# power_supply.net
KiCad netlist of a schematic drawn in Altium Designer
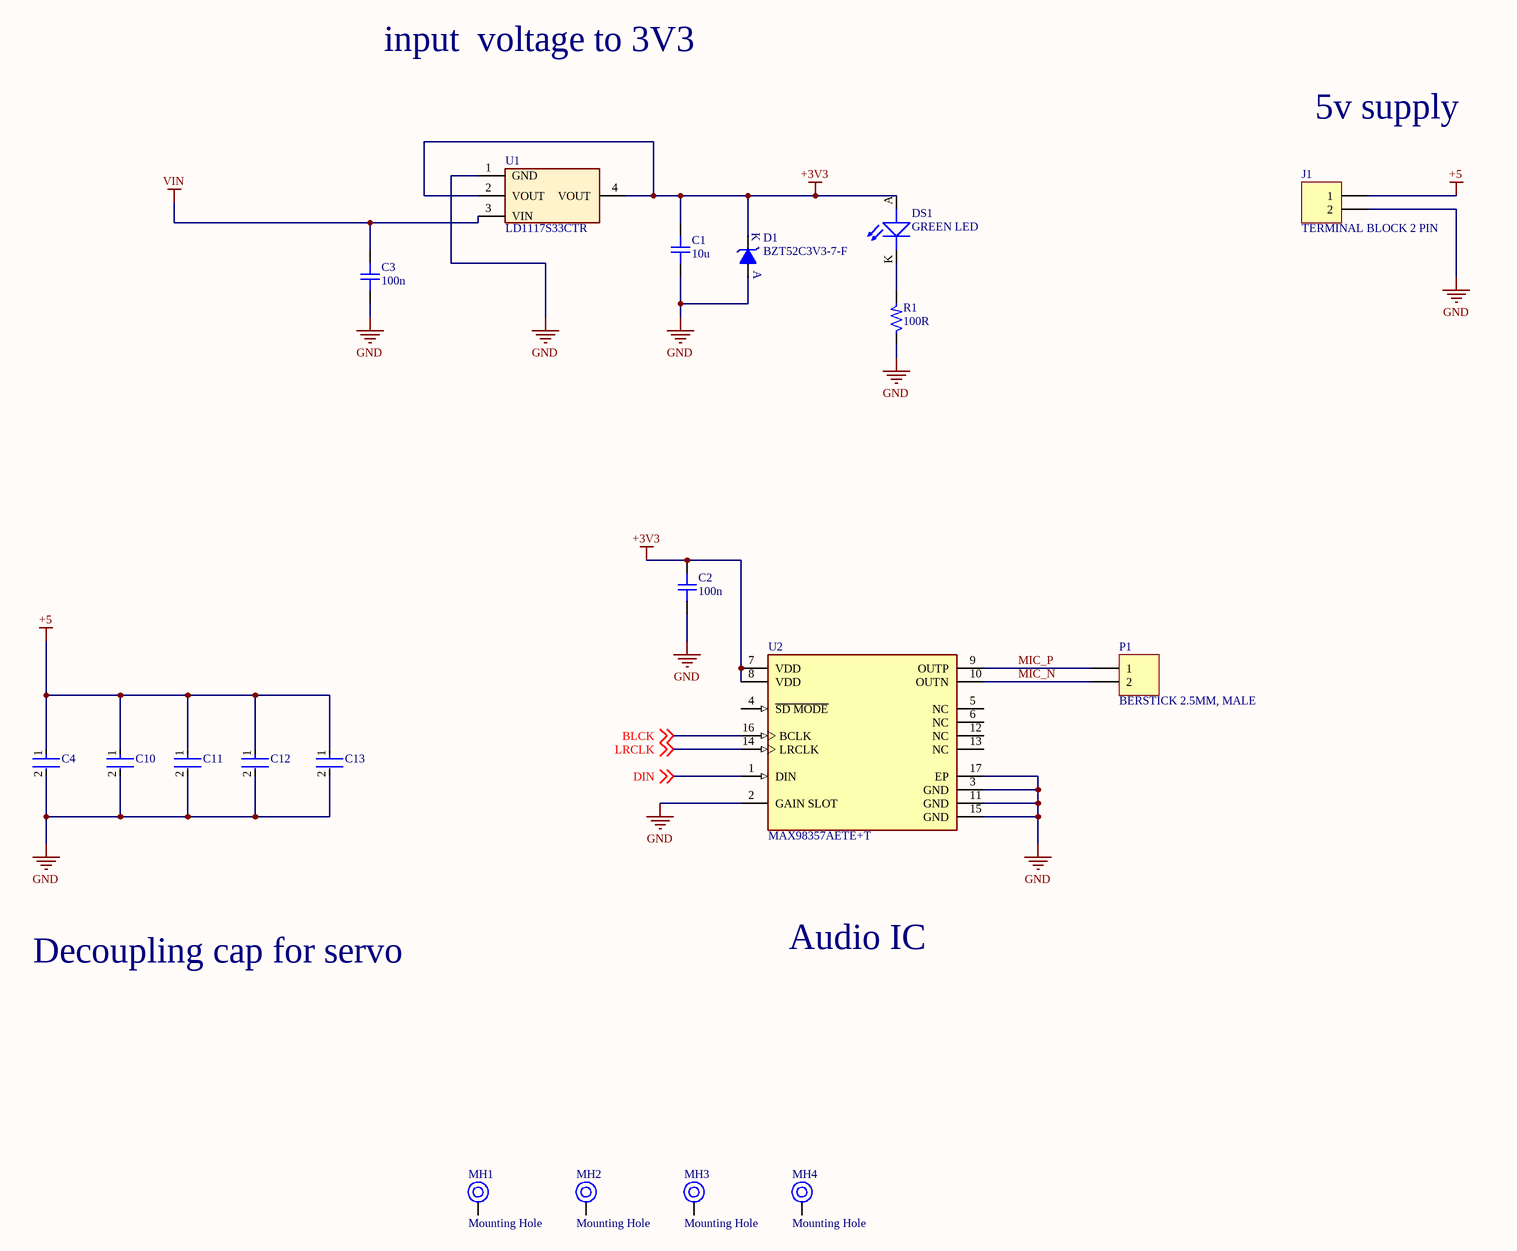
[diagram p0: power supply.SchDoc]

(export (version "E")
  (design (tool "Eeschema 10.0.6"))
  (components
    (comp (ref "C1")
      (value "10u")
      (footprint "CAP_0603")
      (description "Capacitor SMD 0603 10V")
      (fields
        (field (name "MANUFACTURER") "Samsung")
        (field (name "MANUFACTURER PART NUMBER") "CL10A106KP8NNNC")
      )
      (libsource (lib "ESP32_USB_Dongle") (part "CAP_0603_10V"))
    )
    (comp (ref "C2")
      (value "100n")
      (footprint "CAP_0402")
      (description "Capacitor SMD 0402 50V")
      (fields
        (field (name "MANUFACTURER") "Samsung")
        (field (name "MANUFACTURER PART NUMBER") "CL05B104KO5NNNC")
      )
      (libsource (lib "ESP32_USB_Dongle") (part "CAP_0402_50V_1"))
    )
    (comp (ref "C3")
      (value "100n")
      (footprint "CAP_0402")
      (description "Capacitor SMD 0402 50V")
      (fields
        (field (name "MANUFACTURER") "Samsung")
        (field (name "MANUFACTURER PART NUMBER") "CL05B104KO5NNNC")
      )
      (libsource (lib "ESP32_USB_Dongle") (part "CAP_0402_50V_1"))
    )
    (comp (ref "C4")
      (value "C1210C107M9PACTU")
      (footprint "FP-C1210C107M9PACTU-MFG")
      (description "CAP CER 100UF 6.3V X5R 1210")
      (fields (field (name "VOLTAGE") "6.3V") (field (name "TOLERANCE") "20%"))
      (libsource (lib "Altium Content Vault") (part "b4654b650e69147ec39a6b967a45e02"))
    )
    (comp (ref "C10")
      (value "C1210C107M9PACTU")
      (footprint "FP-C1210C107M9PACTU-MFG")
      (description "CAP CER 100UF 6.3V X5R 1210")
      (fields (field (name "VOLTAGE") "6.3V") (field (name "TOLERANCE") "20%"))
      (libsource (lib "Altium Content Vault") (part "b4654b650e69147ec39a6b967a45e02"))
    )
    (comp (ref "C11")
      (value "C1210C107M9PACTU")
      (footprint "FP-C1210C107M9PACTU-MFG")
      (description "CAP CER 100UF 6.3V X5R 1210")
      (fields (field (name "VOLTAGE") "6.3V") (field (name "TOLERANCE") "20%"))
      (libsource (lib "Altium Content Vault") (part "b4654b650e69147ec39a6b967a45e02"))
    )
    (comp (ref "C12")
      (value "C1210C107M9PACTU")
      (footprint "FP-C1210C107M9PACTU-MFG")
      (description "CAP CER 100UF 6.3V X5R 1210")
      (fields (field (name "VOLTAGE") "6.3V") (field (name "TOLERANCE") "20%"))
      (libsource (lib "Altium Content Vault") (part "b4654b650e69147ec39a6b967a45e02"))
    )
    (comp (ref "C13")
      (value "C1210C107M9PACTU")
      (footprint "FP-C1210C107M9PACTU-MFG")
      (description "CAP CER 100UF 6.3V X5R 1210")
      (fields (field (name "VOLTAGE") "6.3V") (field (name "TOLERANCE") "20%"))
      (libsource (lib "Altium Content Vault") (part "b4654b650e69147ec39a6b967a45e02"))
    )
    (comp (ref "D1")
      (value "BZT52C3V3-7-F")
      (footprint "DIO_SOD-123")
      (description "Zener Diode 3.3V 500mW ±6% Surface Mount SOD-123")
      (fields (field (name "MANUFACTURER") "Diodes Incorporated"))
      (libsource (lib "ESTEEMPCBLIB") (part "DIO-Z_3.3V-500mW-SOD123"))
    )
    (comp (ref "DS1")
      (value "GREEN LED")
      (footprint "LED_0805")
      (description "Green 569nm LED Indication - Discrete 2.1V 0805 (2012 Metric)")
      (fields
        (field (name "MANUFACTURER") "Vishay Lite-On")
        (field (name "MANUFACTURER PART NUMBER") "LTST-C171GKT")
      )
      (libsource (lib "ESTEEMPCBLIB") (part "LED_GREEN-2.2-20mA-0805"))
    )
    (comp (ref "J1")
      (value "TERMINAL BLOCK 2 PIN")
      (footprint "CON2_P196_1729128_TH_ST")
      (description "2 Pins, 1 Row 5mm Pitch, straight Connector, male")
      (fields
        (field (name "MANUFACTURER") "Phoenix Contact")
        (field (name "MANUFACTURER PART NUMBER") "MKDSN1,5/2")
      )
      (libsource (lib "ESTEEMPCBLIB") (part "CON-TB_2X1-196-ST-TH"))
    )
    (comp (ref "MH1")
      (value "Mounting Hole")
      (footprint "MOUNTING")
      (fields (field (name "MANUFACTURER PART NUMBER") "NA"))
      (libsource (lib "ESTEEMPCBLIB") (part "MH_3.5H_6D"))
    )
    (comp (ref "MH2")
      (value "Mounting Hole")
      (footprint "MOUNTING")
      (fields (field (name "MANUFACTURER PART NUMBER") "NA"))
      (libsource (lib "ESTEEMPCBLIB") (part "MH_3.5H_6D"))
    )
    (comp (ref "MH3")
      (value "Mounting Hole")
      (footprint "MOUNTING")
      (fields (field (name "MANUFACTURER PART NUMBER") "NA"))
      (libsource (lib "ESTEEMPCBLIB") (part "MH_3.5H_6D"))
    )
    (comp (ref "MH4")
      (value "Mounting Hole")
      (footprint "MOUNTING")
      (fields (field (name "MANUFACTURER PART NUMBER") "NA"))
      (libsource (lib "ESTEEMPCBLIB") (part "MH_3.5H_6D"))
    )
    (comp (ref "P1")
      (value "BERSTICK 2.5MM, MALE")
      (footprint "CON2_100_43D62_TH_ST")
      (description "2 Pins, 1 Row 2.54mm Pitch, Straight bergstrip, Male")
      (fields (field (name "MANUFACTURER PART NUMBER") "NA") (field (name "MANUFACTURER") "Samtec"))
      (libsource (lib "ESTEEMPCBLIB") (part "CON-BS-PLG_2X1-100-ST-TH"))
    )
    (comp (ref "R1")
      (value "100R")
      (footprint "RES_0603")
      (description "100 Ohms ±1% 0.1W, 1/10W Chip Resistor 0603 (1608 Metric) Thick Film")
      (fields (field (name "MANUFACTURER") "Walsin") (field (name "MANUFACTURER PART NUMBER") "WR06X1000FTL"))
      (libsource (lib "ESTEEMPCBLIB") (part "RES_100R-0.1W-1%-0603"))
    )
    (comp (ref "U1")
      (value "LD1117S33CTR")
      (footprint "SOT223_3")
      (description "Linear Voltage Regulator IC 1 Output 800mA SOT-223")
      (fields (field (name "MANUFACTURER") "STMicroelectronics"))
      (libsource (lib "ESTEEMPCBLIB") (part "REG_15V-3.3V-0.9A-12W-SOT223"))
    )
    (comp (ref "U2")
      (value "MAX98357AETE+T")
      (footprint "FP-T1633-4-MFG")
      (description "IC AMP CLASS D MONO 3.2W 16TQFN")
      (libsource (lib "Altium Content Vault") (part "902df0143a84dfa2dd990dcc5368a09"))
    )
  )
  (nets
    (net (code "1") (name "+3V3") (class "Default")
      (node (ref "C1") (pin "2") (pinfunction "2_2") (pintype "passive"))
      (node (ref "C2") (pin "2") (pinfunction "2_2") (pintype "passive"))
      (node (ref "D1") (pin "K") (pinfunction "K_K") (pintype "passive"))
      (node (ref "DS1") (pin "A") (pinfunction "ANODE_A") (pintype "passive"))
      (node (ref "U1") (pin "2") (pinfunction "VOUT_2") (pintype "passive"))
      (node (ref "U1") (pin "4") (pinfunction "VOUT_4") (pintype "passive"))
      (node (ref "U2") (pin "7") (pinfunction "VDD_7") (pintype "power_in"))
      (node (ref "U2") (pin "8") (pinfunction "VDD_8") (pintype "power_in"))
    )
    (net (code "2") (name "+5") (class "Default")
      (node (ref "C10") (pin "1") (pinfunction "1_1") (pintype "passive"))
      (node (ref "C11") (pin "1") (pinfunction "1_1") (pintype "passive"))
      (node (ref "C12") (pin "1") (pinfunction "1_1") (pintype "passive"))
      (node (ref "C13") (pin "1") (pinfunction "1_1") (pintype "passive"))
      (node (ref "C4") (pin "1") (pinfunction "1_1") (pintype "passive"))
      (node (ref "J1") (pin "1") (pinfunction "1_1") (pintype "passive"))
    )
    (net (code "3") (name "/MIC_N") (class "Default")
      (node (ref "P1") (pin "2") (pinfunction "2_2") (pintype "passive"))
      (node (ref "U2") (pin "10") (pinfunction "OUTN_10") (pintype "passive"))
    )
    (net (code "4") (name "/MIC_P") (class "Default")
      (node (ref "P1") (pin "1") (pinfunction "1_1") (pintype "passive"))
      (node (ref "U2") (pin "9") (pinfunction "OUTP_9") (pintype "passive"))
    )
    (net (code "5") (name "BLCK") (class "Default")
      (node (ref "U2") (pin "16") (pinfunction "BCLK_16") (pintype "input"))
    )
    (net (code "6") (name "DIN") (class "Default")
      (node (ref "U2") (pin "1") (pinfunction "DIN_1") (pintype "input"))
    )
    (net (code "7") (name "GND") (class "Default")
      (node (ref "C1") (pin "1") (pinfunction "1_1") (pintype "passive"))
      (node (ref "C10") (pin "2") (pinfunction "2_2") (pintype "passive"))
      (node (ref "C11") (pin "2") (pinfunction "2_2") (pintype "passive"))
      (node (ref "C12") (pin "2") (pinfunction "2_2") (pintype "passive"))
      (node (ref "C13") (pin "2") (pinfunction "2_2") (pintype "passive"))
      (node (ref "C2") (pin "1") (pinfunction "1_1") (pintype "passive"))
      (node (ref "C3") (pin "1") (pinfunction "1_1") (pintype "passive"))
      (node (ref "C4") (pin "2") (pinfunction "2_2") (pintype "passive"))
      (node (ref "D1") (pin "A") (pinfunction "A_A") (pintype "passive"))
      (node (ref "J1") (pin "2") (pinfunction "2_2") (pintype "passive"))
      (node (ref "R1") (pin "1") (pinfunction "1_1") (pintype "passive"))
      (node (ref "U1") (pin "1") (pinfunction "GND_1") (pintype "passive"))
      (node (ref "U2") (pin "11") (pinfunction "GND_11") (pintype "power_in"))
      (node (ref "U2") (pin "15") (pinfunction "GND_15") (pintype "power_in"))
      (node (ref "U2") (pin "17") (pinfunction "EP_17") (pintype "passive"))
      (node (ref "U2") (pin "2") (pinfunction "GAIN_SLOT_2") (pintype "passive"))
      (node (ref "U2") (pin "3") (pinfunction "GND_3") (pintype "power_in"))
    )
    (net (code "8") (name "LRCLK") (class "Default")
      (node (ref "U2") (pin "14") (pinfunction "LRCLK_14") (pintype "input"))
    )
    (net (code "9") (name "Net-(DS1-CATHODE)") (class "Default")
      (node (ref "DS1") (pin "K") (pinfunction "CATHODE_K") (pintype "passive"))
      (node (ref "R1") (pin "2") (pinfunction "2_2") (pintype "passive"))
    )
    (net (code "10") (name "VIN") (class "Default")
      (node (ref "C3") (pin "2") (pinfunction "2_2") (pintype "passive"))
      (node (ref "U1") (pin "3") (pinfunction "VIN_3") (pintype "passive"))
    )
    (net (code "11") (name "unconnected-(MH1-Pad1)") (class "Default")
      (node (ref "MH1") (pin "1") (pinfunction "1_1") (pintype "passive"))
    )
    (net (code "12") (name "unconnected-(MH2-Pad1)") (class "Default")
      (node (ref "MH2") (pin "1") (pinfunction "1_1") (pintype "passive"))
    )
    (net (code "13") (name "unconnected-(MH3-Pad1)") (class "Default")
      (node (ref "MH3") (pin "1") (pinfunction "1_1") (pintype "passive"))
    )
    (net (code "14") (name "unconnected-(MH4-Pad1)") (class "Default")
      (node (ref "MH4") (pin "1") (pinfunction "1_1") (pintype "passive"))
    )
    (net (code "15") (name "unconnected-(U2-NC-Pad5)") (class "Default")
      (node (ref "U2") (pin "5") (pinfunction "NC_5") (pintype "passive"))
    )
    (net (code "16") (name "unconnected-(U2-NC-Pad6)") (class "Default")
      (node (ref "U2") (pin "6") (pinfunction "NC_6") (pintype "passive"))
    )
    (net (code "17") (name "unconnected-(U2-NC-Pad12)") (class "Default")
      (node (ref "U2") (pin "12") (pinfunction "NC_12") (pintype "passive"))
    )
    (net (code "18") (name "unconnected-(U2-NC-Pad13)") (class "Default")
      (node (ref "U2") (pin "13") (pinfunction "NC_13") (pintype "passive"))
    )
    (net (code "19") (name "unconnected-(U2-~{SD_MODE}-Pad4)") (class "Default")
      (node (ref "U2") (pin "4") (pinfunction "~{SD_MODE}_4") (pintype "input"))
    )
  )
)
